# Single-Filter.net
KiCad netlist of a schematic drawn in Altium Designer
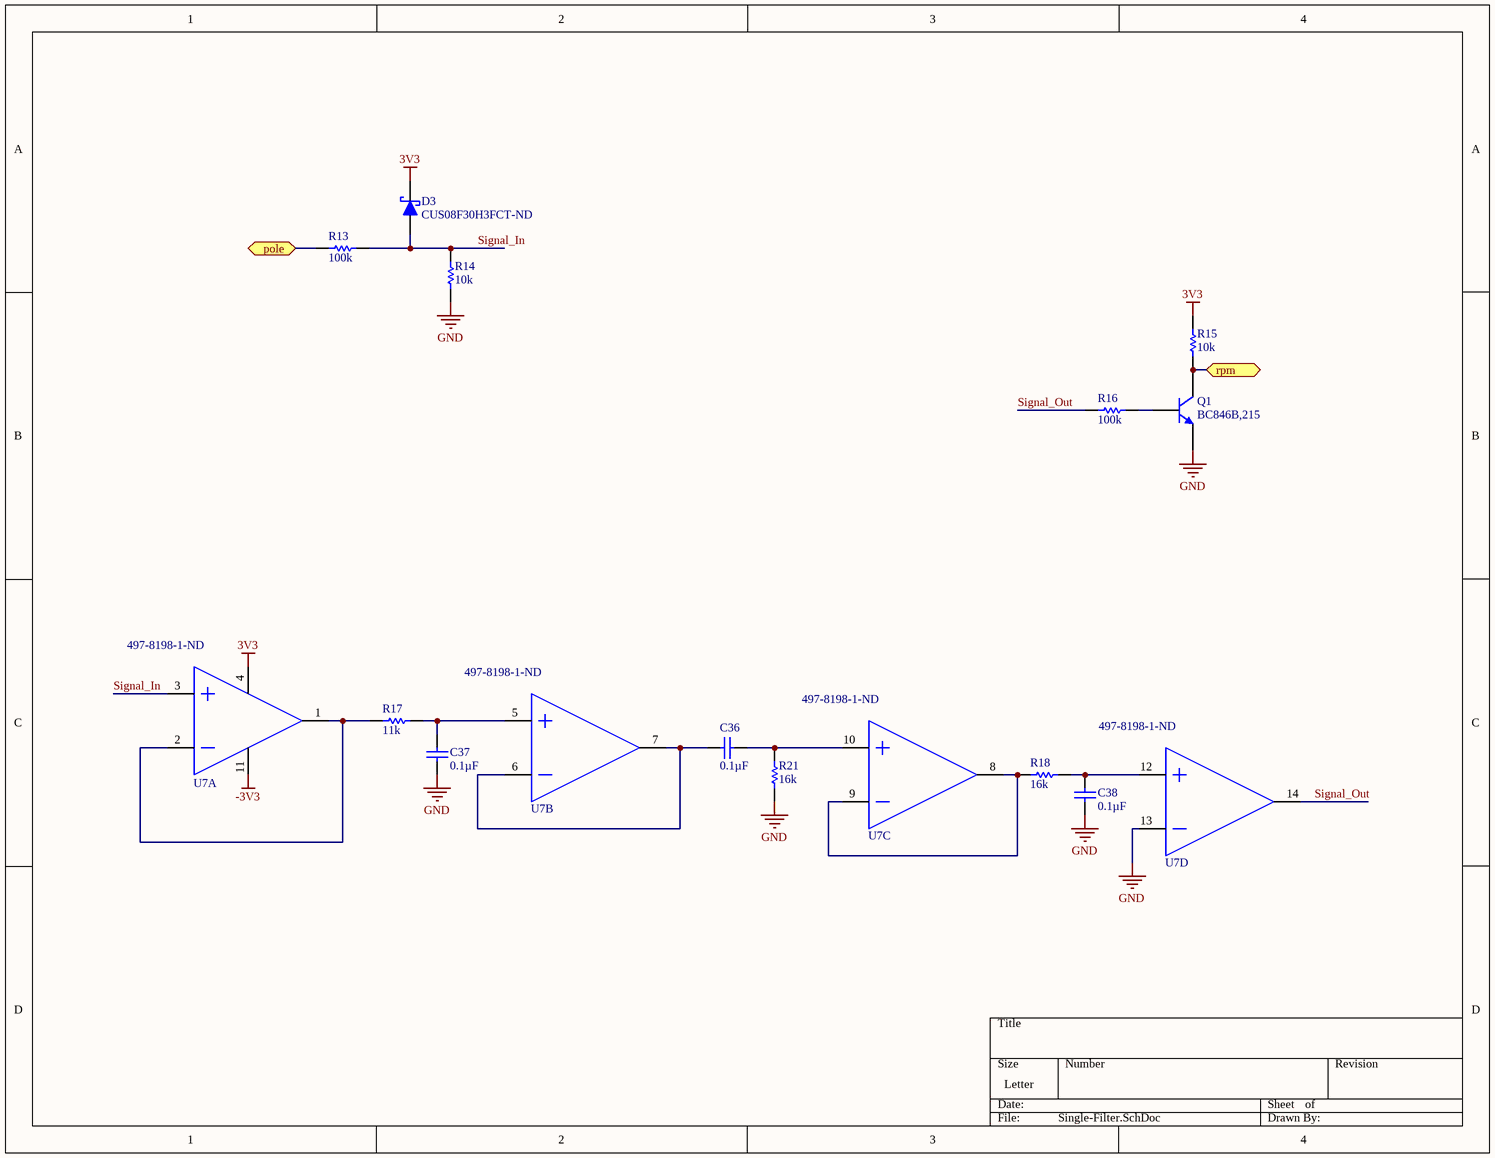
[diagram p0: Single-Filter.SchDoc]

(export (version "E")
  (design (tool "Eeschema 10.0.6"))
  (components
    (comp (ref "C36")
      (value "0.1uF, 50V, 10%, X7R, 1608")
      (footprint "CAPC1608N(0603\")")
      (description "CAP CER 0.1UF 50V 10% X7R 1608 (0603)")
      (fields
        (field (name "MANUFACTURER") "Samsung Electro-Mechanics America, Inc")
        (field (name "MANUFACTURER PART NUMBER") "CL10B104KB8SFNC")
        (field (name "CAPACITANCE") "0.1µF")
      )
      (libsource (lib "AUVic_Integrated_Library_Capacitors") (part "0.1uF, 50V, 10%, X7R, 1608"))
    )
    (comp (ref "C37")
      (value "0.1uF, 50V, 10%, X7R, 1608")
      (footprint "CAPC1608N(0603\")")
      (description "CAP CER 0.1UF 50V 10% X7R 1608 (0603)")
      (fields
        (field (name "MANUFACTURER") "Samsung Electro-Mechanics America, Inc")
        (field (name "MANUFACTURER PART NUMBER") "CL10B104KB8SFNC")
        (field (name "CAPACITANCE") "0.1µF")
      )
      (libsource (lib "AUVic_Integrated_Library_Capacitors") (part "0.1uF, 50V, 10%, X7R, 1608"))
    )
    (comp (ref "C38")
      (value "0.1uF, 50V, 10%, X7R, 1608")
      (footprint "CAPC1608N(0603\")")
      (description "CAP CER 0.1UF 50V 10% X7R 1608 (0603)")
      (fields
        (field (name "MANUFACTURER") "Samsung Electro-Mechanics America, Inc")
        (field (name "MANUFACTURER PART NUMBER") "CL10B104KB8SFNC")
        (field (name "CAPACITANCE") "0.1µF")
      )
      (libsource (lib "AUVic_Integrated_Library_Capacitors") (part "0.1uF, 50V, 10%, X7R, 1608"))
    )
    (comp (ref "D3")
      (value "CUS08F30H3FCT-ND")
      (footprint "SC-76")
      (description "Diode, Schottky, 30V, 800mA")
      (fields
        (field (name "SUPPLIER PART NUMBER 1") "CUS08F30H3FCT-ND")
        (field (name "CREATED BY") "Andy Bates")
        (field (name "PUBLISHER") "AUVic")
      )
      (libsource (lib "AUVic_Integrated_Library_Diodes") (part "CUS08F30H3FCT-ND"))
    )
    (comp (ref "Q1")
      (value "BC846B,215")
      (footprint "SOT-23")
      (description "NPN 65V 100mA 250mW")
      (fields (field (name "PUBLISHER") "Andy Bates"))
      (libsource (lib "AUVic_Integrated_Library_Transistors") (part "BC846B,215"))
    )
    (comp (ref "R13")
      (value "100k")
      (footprint "RESC1608N(0603\")")
      (description "100kR, 1%, 1/10W, 0603 SMD")
      (fields (field (name "MADE BY") "Andy Bates"))
      (libsource (lib "AUVic_Integrated_Library_Resistors") (part "100kR, 1%, 1/10W, 0603 SMD"))
    )
    (comp (ref "R14")
      (value "10k")
      (footprint "RESC1608N(0603\")")
      (description "10kR, 1%, 1/10W, 0603 SMD")
      (fields (field (name "MADE BY") "Ashwin Sira"))
      (libsource (lib "AUVic_Integrated_Library_Resistors") (part "10kR, 1%, 1/10W, 0603 SMD"))
    )
    (comp (ref "R15")
      (value "10k")
      (footprint "RESC1608N(0603\")")
      (description "10kR, 1%, 1/10W, 0603 SMD")
      (fields (field (name "MADE BY") "Ashwin Sira"))
      (libsource (lib "AUVic_Integrated_Library_Resistors") (part "10kR, 1%, 1/10W, 0603 SMD"))
    )
    (comp (ref "R16")
      (value "100k")
      (footprint "RESC1608N(0603\")")
      (description "100kR, 1%, 1/10W, 0603 SMD")
      (fields (field (name "MADE BY") "Andy Bates"))
      (libsource (lib "AUVic_Integrated_Library_Resistors") (part "100kR, 1%, 1/10W, 0603 SMD"))
    )
    (comp (ref "R17")
      (value "11k")
      (footprint "RESC1608N(0603\")")
      (description "11kR, 1%, 1/10W, 0603 SMD")
      (fields (field (name "MADE BY") "Ashwin Sira"))
      (libsource (lib "AUVic_Integrated_Library_Resistors") (part "11kR, 1%, 1/10W, 0603 SMD"))
    )
    (comp (ref "R18")
      (value "16k")
      (footprint "RESC1608N(0603\")")
      (description "16kR, 1%, 1/10W, 0603 SMD")
      (fields (field (name "MADE BY") "Ashwin Sira"))
      (libsource (lib "AUVic_Integrated_Library_Resistors") (part "16kR, 1%, 1/10W, 0603 SMD"))
    )
    (comp (ref "R21")
      (value "16k")
      (footprint "RESC1608N(0603\")")
      (description "16kR, 1%, 1/10W, 0603 SMD")
      (fields (field (name "MADE BY") "Ashwin Sira"))
      (libsource (lib "AUVic_Integrated_Library_Resistors") (part "16kR, 1%, 1/10W, 0603 SMD"))
    )
    (comp (ref "U7")
      (value "Quad Op Amp TSV324")
      (footprint "SOP-14")
      (description "TSV324")
      (fields
        (field (name "SUPPLIER PART NUMBER 1") "497-8198-1-ND")
        (field (name "PUBLISHER") "Altium Limited")
        (field (name "CREATED BY") "Jordan")
      )
      (libsource (lib "AUVic_Integrated_Library_Op_amps") (part "Quad Op Amp TSV324"))
    )
  )
  (nets
    (net (code "1") (name "-3V3") (class "Default")
      (node (ref "U7") (pin "11") (pinfunction "Vcc-_11") (pintype "passive"))
    )
    (net (code "2") (name "/Signal_In") (class "Default")
      (node (ref "D3") (pin "A") (pinfunction "Anode_A") (pintype "passive"))
      (node (ref "R13") (pin "1") (pinfunction "1_1") (pintype "passive"))
      (node (ref "R14") (pin "2") (pinfunction "2_2") (pintype "passive"))
      (node (ref "U7") (pin "3") (pinfunction "Non-Inverting_Input_1_3") (pintype "passive"))
    )
    (net (code "3") (name "/Signal_Out") (class "Default")
      (node (ref "R16") (pin "1") (pinfunction "1_1") (pintype "passive"))
      (node (ref "U7") (pin "14") (pinfunction "Output_4_14") (pintype "passive"))
    )
    (net (code "4") (name "/pole") (class "Default")
      (node (ref "R13") (pin "2") (pinfunction "2_2") (pintype "passive"))
    )
    (net (code "5") (name "/rpm") (class "Default")
      (node (ref "Q1") (pin "3") (pinfunction "C_3") (pintype "passive"))
      (node (ref "R15") (pin "1") (pinfunction "1_1") (pintype "passive"))
    )
    (net (code "6") (name "3V3") (class "Default")
      (node (ref "D3") (pin "K") (pinfunction "Cathode_K") (pintype "passive"))
      (node (ref "R15") (pin "2") (pinfunction "2_2") (pintype "passive"))
      (node (ref "U7") (pin "4") (pinfunction "Vcc+_4") (pintype "passive"))
    )
    (net (code "7") (name "GND") (class "Default")
      (node (ref "C37") (pin "1") (pinfunction "Anode_1") (pintype "passive"))
      (node (ref "C38") (pin "1") (pinfunction "Anode_1") (pintype "passive"))
      (node (ref "Q1") (pin "2") (pinfunction "E_2") (pintype "passive"))
      (node (ref "R14") (pin "1") (pinfunction "1_1") (pintype "passive"))
      (node (ref "R21") (pin "1") (pinfunction "1_1") (pintype "passive"))
      (node (ref "U7") (pin "13") (pinfunction "Inverting_Input_3_13") (pintype "passive"))
    )
    (net (code "8") (name "Net-(C36-Anode)") (class "Default")
      (node (ref "C36") (pin "1") (pinfunction "Anode_1") (pintype "passive"))
      (node (ref "U7") (pin "6") (pinfunction "Inverting_Input_2_6") (pintype "passive"))
      (node (ref "U7") (pin "7") (pinfunction "Output_2_7") (pintype "passive"))
    )
    (net (code "9") (name "Net-(C36-Cathode)") (class "Default")
      (node (ref "C36") (pin "2") (pinfunction "Cathode_2") (pintype "passive"))
      (node (ref "R21") (pin "2") (pinfunction "2_2") (pintype "passive"))
      (node (ref "U7") (pin "10") (pinfunction "Non-Inverting_Input_3_10") (pintype "passive"))
    )
    (net (code "10") (name "Net-(C37-Cathode)") (class "Default")
      (node (ref "C37") (pin "2") (pinfunction "Cathode_2") (pintype "passive"))
      (node (ref "R17") (pin "2") (pinfunction "2_2") (pintype "passive"))
      (node (ref "U7") (pin "5") (pinfunction "Non-Inverting_Input_2_5") (pintype "passive"))
    )
    (net (code "11") (name "Net-(C38-Cathode)") (class "Default")
      (node (ref "C38") (pin "2") (pinfunction "Cathode_2") (pintype "passive"))
      (node (ref "R18") (pin "1") (pinfunction "1_1") (pintype "passive"))
      (node (ref "U7") (pin "12") (pinfunction "Non-Inverting_Input_4_12") (pintype "passive"))
    )
    (net (code "12") (name "Net-(Q1-B)") (class "Default")
      (node (ref "Q1") (pin "1") (pinfunction "B_1") (pintype "passive"))
      (node (ref "R16") (pin "2") (pinfunction "2_2") (pintype "passive"))
    )
    (net (code "13") (name "Net-(U7A-Inverting_Input_1)") (class "Default")
      (node (ref "R17") (pin "1") (pinfunction "1_1") (pintype "passive"))
      (node (ref "U7") (pin "1") (pinfunction "Output_1_1") (pintype "passive"))
      (node (ref "U7") (pin "2") (pinfunction "Inverting_Input_1_2") (pintype "passive"))
    )
    (net (code "14") (name "Net-(U7C-Inverting_Input_3)") (class "Default")
      (node (ref "R18") (pin "2") (pinfunction "2_2") (pintype "passive"))
      (node (ref "U7") (pin "8") (pinfunction "Output_3_8") (pintype "passive"))
      (node (ref "U7") (pin "9") (pinfunction "Inverting_Input_3_9") (pintype "passive"))
    )
  )
)
